# 03_-_POWER_SUPLY.net
KiCad netlist of a schematic drawn in Altium Designer
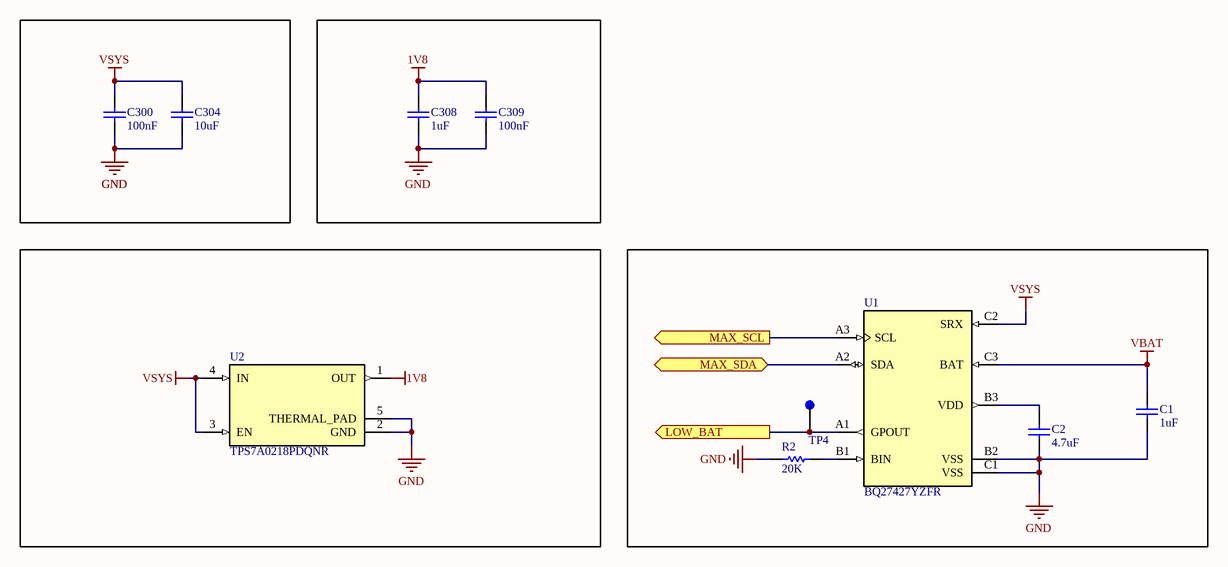
[diagram p0: 03 - POWER SUPLY.SchDoc]

(export (version "E")
  (design (tool "Eeschema 10.0.6"))
  (components
    (comp (ref "C1")
      (value "1uF")
      (footprint "0402-C-R")
      (description "CAP SMD 0402 MLCC GERAL 1uF 25V ±10% 0402 X5R PN:GRM155R61E105KA12D MURATA")
      (fields (field (name "VOLTAGE") "25V") (field (name "TOLERANCE") "10%"))
      (libsource (lib "Schlib1") (part "CAP SMD 0402 1uF 25V ±10%"))
    )
    (comp (ref "C2")
      (value "4.7uF")
      (footprint "0402-C-R")
      (description "CAP SMD 0402 MLCC GERAL 4.7uF 10V ±20% 0402 X5R PN:GRM155R61A475MEAAD MURATA")
      (fields (field (name "VOLTAGE") "10V") (field (name "TOLERANCE") "20%"))
      (libsource (lib "Schlib1") (part "CAP SMD 0402 4.7uF 10V ±20%"))
    )
    (comp (ref "C300")
      (value "100nF")
      (footprint "0402-C-R")
      (description "CAP SMD 0402 MLCC GERAL 100nF 10V ±20% 0402 X7R PN:C0402C104K8RACTU KEMET")
      (fields (field (name "VOLTAGE") "10V") (field (name "TOLERANCE") "20%"))
      (libsource (lib "Schlib1") (part "CAP SMD 0402 100nF 10V ±20%"))
    )
    (comp (ref "C304")
      (value "10uF")
      (footprint "0603-C-R")
      (description "CAP SMD 0603 MLCC GERAL 10uF 10V ±10% X7R PN: GRM188Z71A106KA73D")
      (fields (field (name "VOLTAGE") "10V") (field (name "TOLERANCE") "10%"))
      (libsource (lib "Schlib1") (part "CAP SMD 0603 10uF 10V ±10%"))
    )
    (comp (ref "C308")
      (value "1uF")
      (footprint "0402-C-R")
      (description "CAP SMD 0402 MLCC GERAL 1uF 25V ±10% 0402 X5R PN:GRM155R61E105KA12D MURATA")
      (fields (field (name "VOLTAGE") "25V") (field (name "TOLERANCE") "10%"))
      (libsource (lib "Schlib1") (part "CAP SMD 0402 1uF 25V ±10%"))
    )
    (comp (ref "C309")
      (value "100nF")
      (footprint "0402-C-R")
      (description "CAP SMD 0402 MLCC GERAL 100nF 10V ±20% 0402 X7R PN:C0402C104K8RACTU KEMET")
      (fields (field (name "VOLTAGE") "10V") (field (name "TOLERANCE") "20%"))
      (libsource (lib "Schlib1") (part "CAP SMD 0402 100nF 10V ±20%"))
    )
    (comp (ref "R2")
      (value "20K")
      (footprint "0402-R-R")
      (description "RES SMD GERAL FILM 20K 0.063W ±1% 0402 7\" TAPE PN: RMCF0402FT20K0 STACKPOLE")
      (fields (field (name "POWER") "0.063W") (field (name "TOLERANCE") "1%"))
      (libsource (lib "Schlib1") (part "RES SMD 0402 20K 0.063W ±1%"))
    )
    (comp (ref "TP4")
      (value "TEST POINT SMD")
      (footprint "TP SMD")
      (libsource (lib "Schlib1") (part "TEST POINT SMD"))
    )
    (comp (ref "U1")
      (value "IC SINGLE-CELL BATTERY FUEL GAUGE W")
      (footprint "IC_BQ27427YZFR")
      (description "Battery Fuel Gauge IC Lithium Ion 9-DSBGA PN: BQ27427YZFR")
      (fields (field (name "PN") "BQ27427YZFR") (field (name "MF") "Texas Instruments"))
      (libsource (lib "Schlib1") (part "IC SINGLE-CELL BATTERY FUEL GAUGE W"))
    )
    (comp (ref "U2")
      (value "IC REG LINEAR 1.8V 200MA 4-X2SON")
      (footprint "IC_TPS7A0218PDQNR")
      (description "Linear Voltage Regulator IC Positive Fixed 1 Output 200mA 4-X2SON (1x1) PN: TPS7A0218PDQNR")
      (fields
        (field (name "MF") "{'manufacturer': u'Texas Instruments'}")
        (field (name "PN") "TPS7A0218PDQNR")
      )
      (libsource (lib "Schlib1") (part "IC REG LINEAR 1.8V 200MA 4-X2SON"))
    )
  )
  (nets
    (net (code "1") (name "/LOW_BAT") (class "Default")
      (node (ref "TP4") (pin "1") (pinfunction "TP_1") (pintype "passive"))
      (node (ref "U1") (pin "A1") (pinfunction "GPOUT_A1") (pintype "output"))
    )
    (net (code "2") (name "/MAX_SCL") (class "Default")
      (node (ref "U1") (pin "A3") (pinfunction "SCL_A3") (pintype "input"))
    )
    (net (code "3") (name "/MAX_SDA") (class "Default")
      (node (ref "U1") (pin "A2") (pinfunction "SDA_A2") (pintype "bidirectional"))
    )
    (net (code "4") (name "1V8") (class "Default")
      (node (ref "C308") (pin "2") (pinfunction "2_2") (pintype "passive"))
      (node (ref "C309") (pin "2") (pinfunction "2_2") (pintype "passive"))
      (node (ref "U2") (pin "1") (pinfunction "OUT_1") (pintype "output"))
    )
    (net (code "5") (name "GND") (class "Default")
      (node (ref "C1") (pin "1") (pinfunction "1_1") (pintype "passive"))
      (node (ref "C2") (pin "1") (pinfunction "1_1") (pintype "passive"))
      (node (ref "C300") (pin "1") (pinfunction "1_1") (pintype "passive"))
      (node (ref "C304") (pin "1") (pinfunction "1_1") (pintype "passive"))
      (node (ref "C308") (pin "1") (pinfunction "1_1") (pintype "passive"))
      (node (ref "C309") (pin "1") (pinfunction "1_1") (pintype "passive"))
      (node (ref "R2") (pin "1") (pinfunction "1_1") (pintype "passive"))
      (node (ref "U1") (pin "B2") (pinfunction "VSS_B2") (pintype "power_in"))
      (node (ref "U1") (pin "C1") (pinfunction "VSS_C1") (pintype "power_in"))
      (node (ref "U2") (pin "2") (pinfunction "GND_2") (pintype "power_in"))
      (node (ref "U2") (pin "5") (pinfunction "THERMAL_PAD_5") (pintype "power_in"))
    )
    (net (code "6") (name "Net-(U1-BIN)") (class "Default")
      (node (ref "R2") (pin "2") (pinfunction "2_2") (pintype "passive"))
      (node (ref "U1") (pin "B1") (pinfunction "BIN_B1") (pintype "input"))
    )
    (net (code "7") (name "Net-(U1-VDD)") (class "Default")
      (node (ref "C2") (pin "2") (pinfunction "2_2") (pintype "passive"))
      (node (ref "U1") (pin "B3") (pinfunction "VDD_B3") (pintype "output"))
    )
    (net (code "8") (name "VBAT") (class "Default")
      (node (ref "C1") (pin "2") (pinfunction "2_2") (pintype "passive"))
      (node (ref "U1") (pin "C3") (pinfunction "BAT_C3") (pintype "input"))
    )
    (net (code "9") (name "VSYS") (class "Default")
      (node (ref "C300") (pin "2") (pinfunction "2_2") (pintype "passive"))
      (node (ref "C304") (pin "2") (pinfunction "2_2") (pintype "passive"))
      (node (ref "U1") (pin "C2") (pinfunction "SRX_C2") (pintype "input"))
      (node (ref "U2") (pin "3") (pinfunction "EN_3") (pintype "input"))
      (node (ref "U2") (pin "4") (pinfunction "IN_4") (pintype "input"))
    )
  )
)
